# Conn_A.net
KiCad netlist of a schematic drawn in Altium Designer
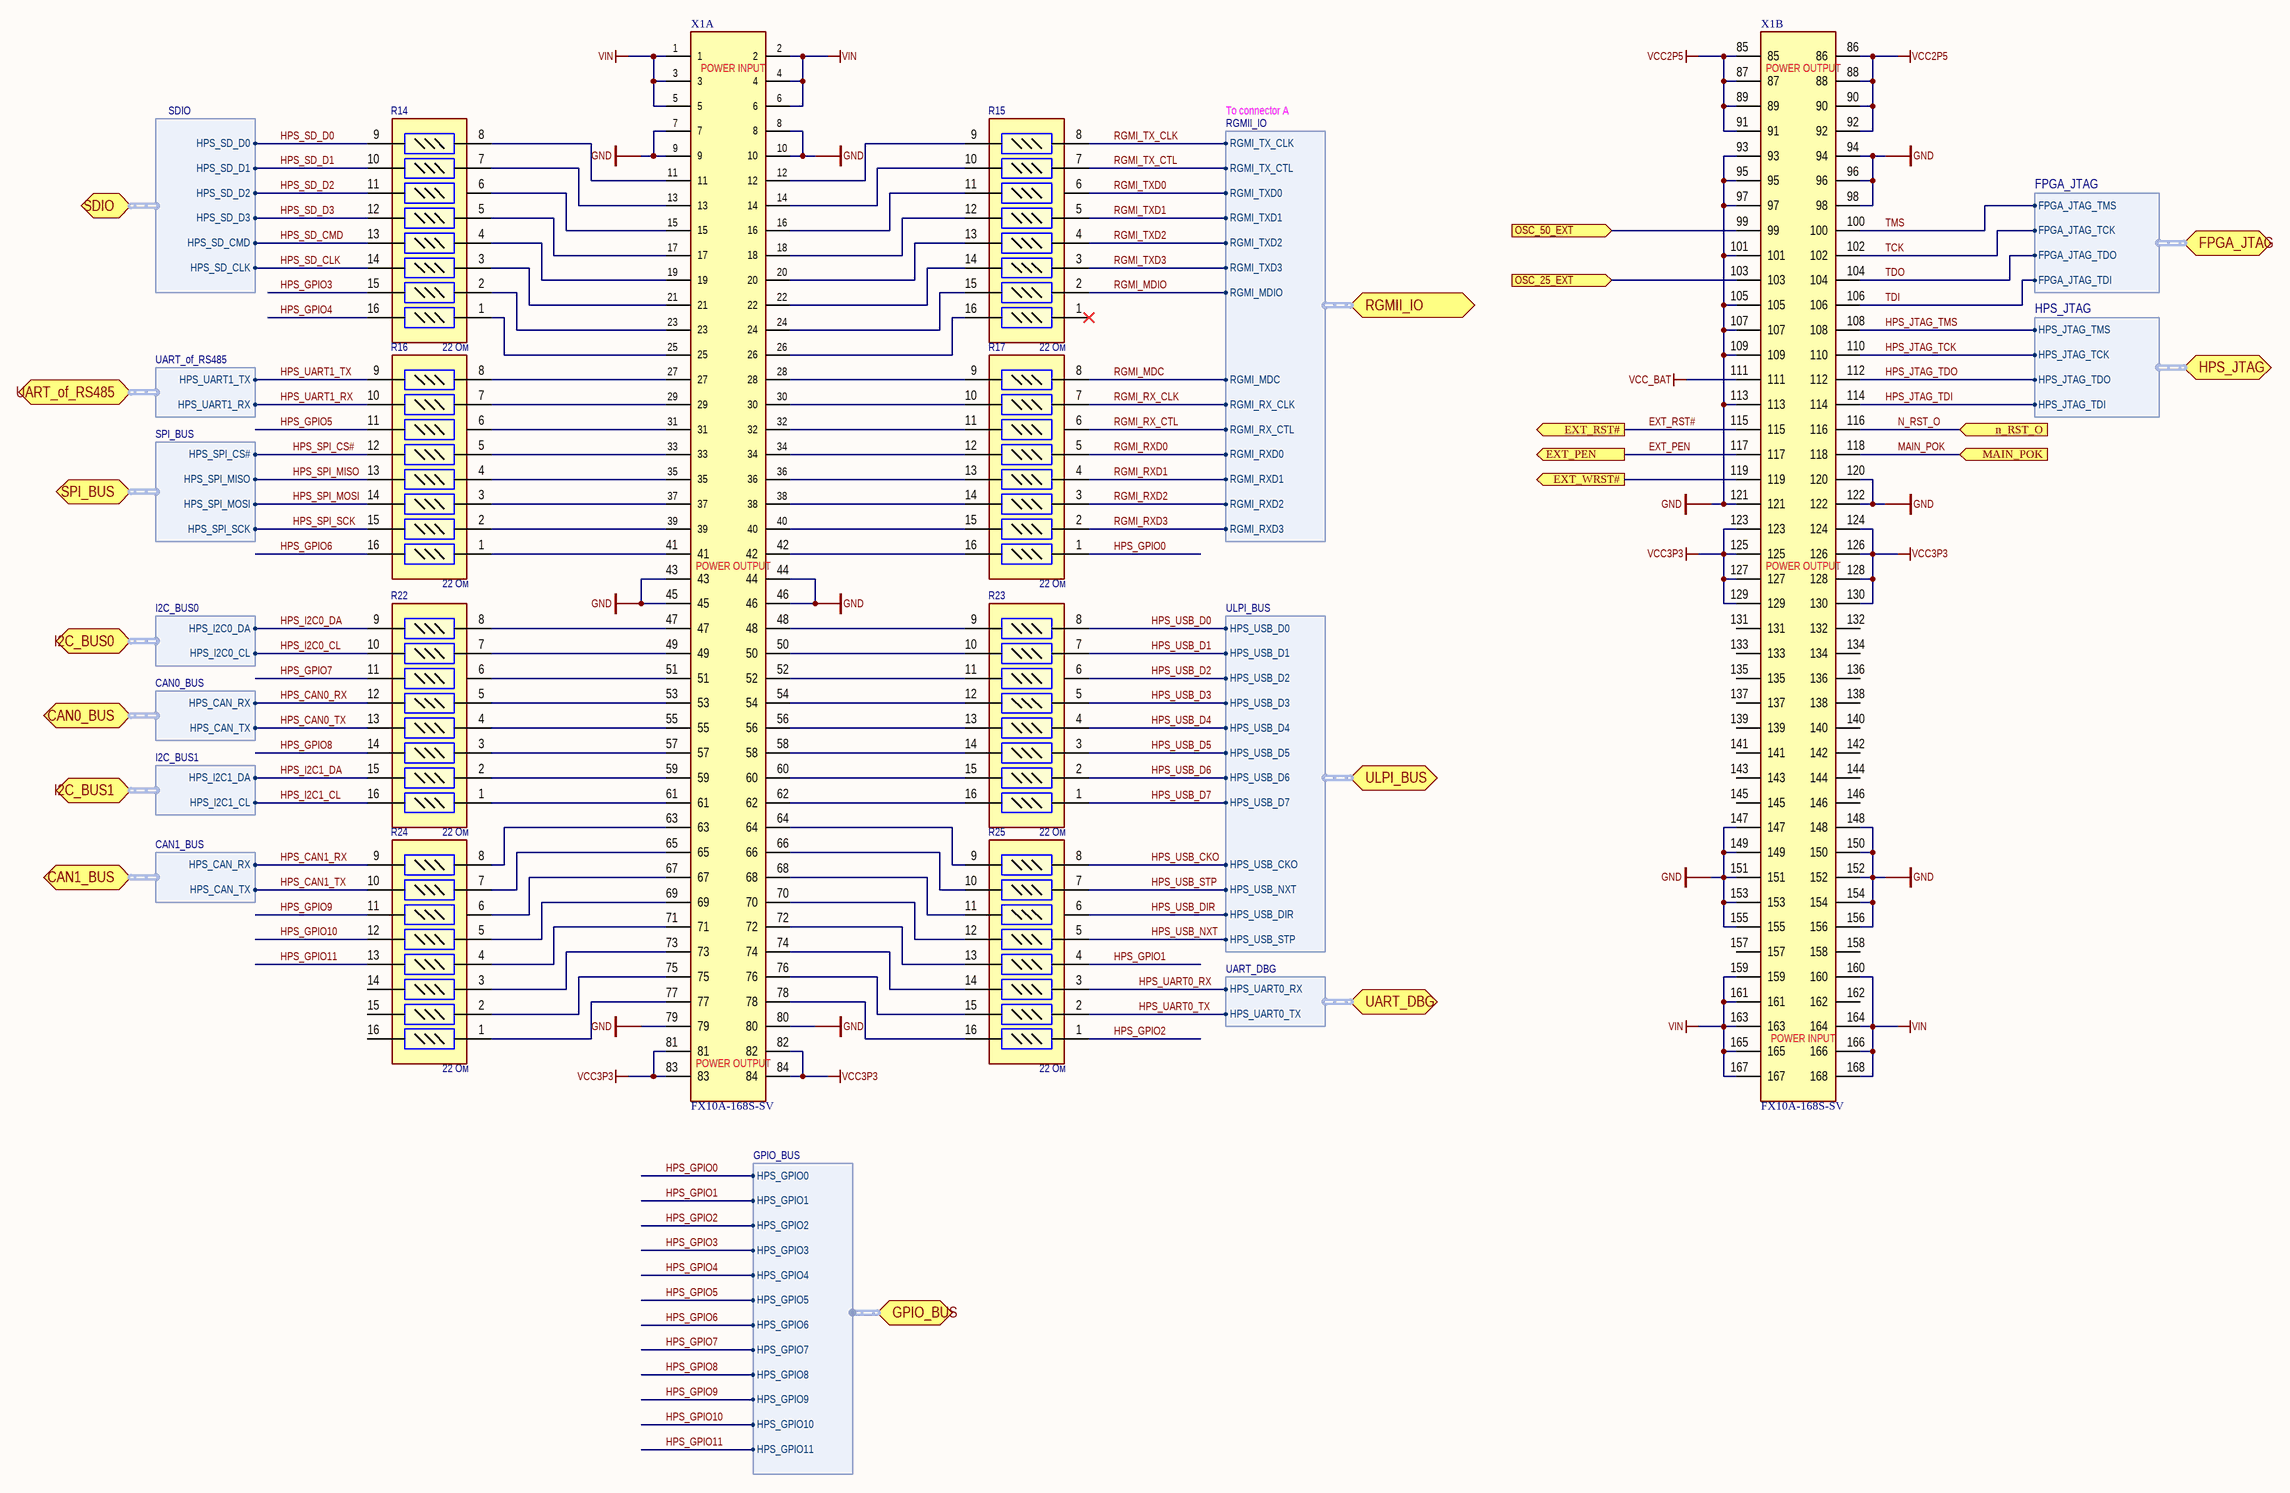
[diagram p0: Conn_A.SchDoc]

(export (version "E")
  (design (tool "Eeschema 10.0.6"))
  (components
    (comp (ref "R14")
      (value "22 Ом")
      (footprint "CAT16-J8")
      (description "Набор чип резисторов")
      (fields (field (name "Comment") "YC248-JR-07-22 Ом"))
      (libsource (lib "SD_IC") (part "YC248-JR-07-#"))
    )
    (comp (ref "R15")
      (value "22 Ом")
      (footprint "CAT16-J8")
      (description "Набор чип резисторов")
      (fields (field (name "Comment") "YC248-JR-07-22 Ом"))
      (libsource (lib "SD_IC") (part "YC248-JR-07-#"))
    )
    (comp (ref "R16")
      (value "22 Ом")
      (footprint "CAT16-J8")
      (description "Набор чип резисторов")
      (fields (field (name "Comment") "YC248-JR-07-22 Ом"))
      (libsource (lib "SD_IC") (part "YC248-JR-07-#"))
    )
    (comp (ref "R17")
      (value "22 Ом")
      (footprint "CAT16-J8")
      (description "Набор чип резисторов")
      (fields (field (name "Comment") "YC248-JR-07-22 Ом"))
      (libsource (lib "SD_IC") (part "YC248-JR-07-#"))
    )
    (comp (ref "R22")
      (value "22 Ом")
      (footprint "CAT16-J8")
      (description "Набор чип резисторов")
      (fields (field (name "Comment") "YC248-JR-07-22 Ом"))
      (libsource (lib "SD_IC") (part "YC248-JR-07-#"))
    )
    (comp (ref "R23")
      (value "22 Ом")
      (footprint "CAT16-J8")
      (description "Набор чип резисторов")
      (fields (field (name "Comment") "YC248-JR-07-22 Ом"))
      (libsource (lib "SD_IC") (part "YC248-JR-07-#"))
    )
    (comp (ref "R24")
      (value "22 Ом")
      (footprint "CAT16-J8")
      (description "Набор чип резисторов")
      (fields (field (name "Comment") "YC248-JR-07-22 Ом"))
      (libsource (lib "SD_IC") (part "YC248-JR-07-#"))
    )
    (comp (ref "R25")
      (value "22 Ом")
      (footprint "CAT16-J8")
      (description "Набор чип резисторов")
      (fields (field (name "Comment") "YC248-JR-07-22 Ом"))
      (libsource (lib "SD_IC") (part "YC248-JR-07-#"))
    )
    (comp (ref "X1")
      (value "FX10A-168S-SV")
      (footprint "FX10A-168S-SV")
      (libsource (lib "SD_IC") (part "FX10A-168S-SV"))
    )
  )
  (nets
    (net (code "14") (name "/EXT_PEN") (class "Default")
      (node (ref "X1") (pin "117") (pinfunction "117_117") (pintype "passive"))
    )
    (net (code "15") (name "/EXT_RST#") (class "Default")
      (node (ref "X1") (pin "115") (pinfunction "115_115") (pintype "passive"))
    )
    (net (code "16") (name "/EXT_WRST#") (class "Default")
      (node (ref "X1") (pin "119") (pinfunction "119_119") (pintype "passive"))
    )
    (net (code "17") (name "/HPS_CAN0_RX") (class "Default")
      (node (ref "R22") (pin "12") (pintype "passive"))
    )
    (net (code "18") (name "/HPS_CAN0_TX") (class "Default")
      (node (ref "R22") (pin "13") (pintype "passive"))
    )
    (net (code "19") (name "/HPS_CAN1_RX") (class "Default") (node (ref "R24") (pin "9") (pintype "passive")))
    (net (code "20") (name "/HPS_CAN1_TX") (class "Default")
      (node (ref "R24") (pin "10") (pintype "passive"))
    )
    (net (code "21") (name "/HPS_GPIO0") (class "Default") (node (ref "R17") (pin "1") (pintype "passive")))
    (net (code "22") (name "/HPS_GPIO1") (class "Default") (node (ref "R25") (pin "4") (pintype "passive")))
    (net (code "23") (name "/HPS_GPIO2") (class "Default") (node (ref "R25") (pin "1") (pintype "passive")))
    (net (code "24") (name "/HPS_GPIO3") (class "Default") (node (ref "R14") (pin "15") (pintype "passive")))
    (net (code "25") (name "/HPS_GPIO4") (class "Default") (node (ref "R14") (pin "16") (pintype "passive")))
    (net (code "26") (name "/HPS_GPIO5") (class "Default") (node (ref "R16") (pin "11") (pintype "passive")))
    (net (code "27") (name "/HPS_GPIO6") (class "Default") (node (ref "R16") (pin "16") (pintype "passive")))
    (net (code "28") (name "/HPS_GPIO7") (class "Default") (node (ref "R22") (pin "11") (pintype "passive")))
    (net (code "29") (name "/HPS_GPIO8") (class "Default") (node (ref "R22") (pin "14") (pintype "passive")))
    (net (code "30") (name "/HPS_GPIO9") (class "Default") (node (ref "R24") (pin "11") (pintype "passive")))
    (net (code "31") (name "/HPS_GPIO10") (class "Default") (node (ref "R24") (pin "12") (pintype "passive")))
    (net (code "32") (name "/HPS_GPIO11") (class "Default") (node (ref "R24") (pin "13") (pintype "passive")))
    (net (code "33") (name "/HPS_I2C0_CL") (class "Default")
      (node (ref "R22") (pin "10") (pintype "passive"))
    )
    (net (code "34") (name "/HPS_I2C0_DA") (class "Default") (node (ref "R22") (pin "9") (pintype "passive")))
    (net (code "35") (name "/HPS_I2C1_CL") (class "Default")
      (node (ref "R22") (pin "16") (pintype "passive"))
    )
    (net (code "36") (name "/HPS_I2C1_DA") (class "Default")
      (node (ref "R22") (pin "15") (pintype "passive"))
    )
    (net (code "37") (name "/HPS_JTAG_TCK") (class "Default")
      (node (ref "X1") (pin "110") (pinfunction "110_110") (pintype "passive"))
    )
    (net (code "38") (name "/HPS_JTAG_TDI") (class "Default")
      (node (ref "X1") (pin "114") (pinfunction "114_114") (pintype "passive"))
    )
    (net (code "39") (name "/HPS_JTAG_TDO") (class "Default")
      (node (ref "X1") (pin "112") (pinfunction "112_112") (pintype "passive"))
    )
    (net (code "40") (name "/HPS_JTAG_TMS") (class "Default")
      (node (ref "X1") (pin "108") (pinfunction "108_108") (pintype "passive"))
    )
    (net (code "41") (name "/HPS_SD_CLK") (class "Default") (node (ref "R14") (pin "14") (pintype "passive")))
    (net (code "42") (name "/HPS_SD_CMD") (class "Default") (node (ref "R14") (pin "13") (pintype "passive")))
    (net (code "43") (name "/HPS_SD_D0") (class "Default") (node (ref "R14") (pin "9") (pintype "passive")))
    (net (code "44") (name "/HPS_SD_D1") (class "Default") (node (ref "R14") (pin "10") (pintype "passive")))
    (net (code "45") (name "/HPS_SD_D2") (class "Default") (node (ref "R14") (pin "11") (pintype "passive")))
    (net (code "46") (name "/HPS_SD_D3") (class "Default") (node (ref "R14") (pin "12") (pintype "passive")))
    (net (code "47") (name "/HPS_SPI_CS#") (class "Default")
      (node (ref "R16") (pin "12") (pintype "passive"))
    )
    (net (code "48") (name "/HPS_SPI_MISO") (class "Default")
      (node (ref "R16") (pin "13") (pintype "passive"))
    )
    (net (code "49") (name "/HPS_SPI_MOSI") (class "Default")
      (node (ref "R16") (pin "14") (pintype "passive"))
    )
    (net (code "50") (name "/HPS_SPI_SCK") (class "Default")
      (node (ref "R16") (pin "15") (pintype "passive"))
    )
    (net (code "51") (name "/HPS_UART0_RX") (class "Default")
      (node (ref "R25") (pin "3") (pintype "passive"))
    )
    (net (code "52") (name "/HPS_UART0_TX") (class "Default")
      (node (ref "R25") (pin "2") (pintype "passive"))
    )
    (net (code "53") (name "/HPS_UART1_RX") (class "Default")
      (node (ref "R16") (pin "10") (pintype "passive"))
    )
    (net (code "54") (name "/HPS_UART1_TX") (class "Default")
      (node (ref "R16") (pin "9") (pintype "passive"))
    )
    (net (code "55") (name "/HPS_USB_CKO") (class "Default") (node (ref "R25") (pin "8") (pintype "passive")))
    (net (code "56") (name "/HPS_USB_D0") (class "Default") (node (ref "R23") (pin "8") (pintype "passive")))
    (net (code "57") (name "/HPS_USB_D1") (class "Default") (node (ref "R23") (pin "7") (pintype "passive")))
    (net (code "58") (name "/HPS_USB_D2") (class "Default") (node (ref "R23") (pin "6") (pintype "passive")))
    (net (code "59") (name "/HPS_USB_D3") (class "Default") (node (ref "R23") (pin "5") (pintype "passive")))
    (net (code "60") (name "/HPS_USB_D4") (class "Default") (node (ref "R23") (pin "4") (pintype "passive")))
    (net (code "61") (name "/HPS_USB_D5") (class "Default") (node (ref "R23") (pin "3") (pintype "passive")))
    (net (code "62") (name "/HPS_USB_D6") (class "Default") (node (ref "R23") (pin "2") (pintype "passive")))
    (net (code "63") (name "/HPS_USB_D7") (class "Default") (node (ref "R23") (pin "1") (pintype "passive")))
    (net (code "64") (name "/HPS_USB_DIR") (class "Default") (node (ref "R25") (pin "6") (pintype "passive")))
    (net (code "65") (name "/HPS_USB_NXT") (class "Default") (node (ref "R25") (pin "5") (pintype "passive")))
    (net (code "66") (name "/HPS_USB_STP") (class "Default") (node (ref "R25") (pin "7") (pintype "passive")))
    (net (code "67") (name "/MAIN_POK") (class "Default")
      (node (ref "X1") (pin "118") (pinfunction "118_118") (pintype "passive"))
    )
    (net (code "68") (name "/N_RST_O") (class "Default")
      (node (ref "X1") (pin "116") (pinfunction "116_116") (pintype "passive"))
    )
    (net (code "69") (name "/OSC_25_EXT") (class "Default")
      (node (ref "X1") (pin "103") (pinfunction "103_103") (pintype "passive"))
    )
    (net (code "70") (name "/OSC_50_EXT") (class "Default")
      (node (ref "X1") (pin "99") (pinfunction "99_99") (pintype "passive"))
    )
    (net (code "71") (name "/RGMI_MDC") (class "Default") (node (ref "R17") (pin "8") (pintype "passive")))
    (net (code "72") (name "/RGMI_MDIO") (class "Default") (node (ref "R15") (pin "2") (pintype "passive")))
    (net (code "73") (name "/RGMI_RXD0") (class "Default") (node (ref "R17") (pin "5") (pintype "passive")))
    (net (code "74") (name "/RGMI_RXD1") (class "Default") (node (ref "R17") (pin "4") (pintype "passive")))
    (net (code "75") (name "/RGMI_RXD2") (class "Default") (node (ref "R17") (pin "3") (pintype "passive")))
    (net (code "76") (name "/RGMI_RXD3") (class "Default") (node (ref "R17") (pin "2") (pintype "passive")))
    (net (code "77") (name "/RGMI_RX_CLK") (class "Default") (node (ref "R17") (pin "7") (pintype "passive")))
    (net (code "78") (name "/RGMI_RX_CTL") (class "Default") (node (ref "R17") (pin "6") (pintype "passive")))
    (net (code "79") (name "/RGMI_TXD0") (class "Default") (node (ref "R15") (pin "6") (pintype "passive")))
    (net (code "80") (name "/RGMI_TXD1") (class "Default") (node (ref "R15") (pin "5") (pintype "passive")))
    (net (code "81") (name "/RGMI_TXD2") (class "Default") (node (ref "R15") (pin "4") (pintype "passive")))
    (net (code "82") (name "/RGMI_TXD3") (class "Default") (node (ref "R15") (pin "3") (pintype "passive")))
    (net (code "83") (name "/RGMI_TX_CLK") (class "Default") (node (ref "R15") (pin "8") (pintype "passive")))
    (net (code "84") (name "/RGMI_TX_CTL") (class "Default") (node (ref "R15") (pin "7") (pintype "passive")))
    (net (code "85") (name "/TCK") (class "Default")
      (node (ref "X1") (pin "102") (pinfunction "102_102") (pintype "passive"))
    )
    (net (code "86") (name "/TDI") (class "Default")
      (node (ref "X1") (pin "106") (pinfunction "106_106") (pintype "passive"))
    )
    (net (code "87") (name "/TDO") (class "Default")
      (node (ref "X1") (pin "104") (pinfunction "104_104") (pintype "passive"))
    )
    (net (code "88") (name "/TMS") (class "Default")
      (node (ref "X1") (pin "100") (pinfunction "100_100") (pintype "passive"))
    )
    (net (code "102") (name "GND") (class "Default")
      (node (ref "X1") (pin "10") (pinfunction "10_10") (pintype "passive"))
      (node (ref "X1") (pin "101") (pinfunction "101_101") (pintype "passive"))
      (node (ref "X1") (pin "105") (pinfunction "105_105") (pintype "passive"))
      (node (ref "X1") (pin "107") (pinfunction "107_107") (pintype "passive"))
      (node (ref "X1") (pin "109") (pinfunction "109_109") (pintype "passive"))
      (node (ref "X1") (pin "113") (pinfunction "113_113") (pintype "passive"))
      (node (ref "X1") (pin "120") (pinfunction "120_120") (pintype "passive"))
      (node (ref "X1") (pin "121") (pinfunction "121_121") (pintype "passive"))
      (node (ref "X1") (pin "122") (pinfunction "122_122") (pintype "passive"))
      (node (ref "X1") (pin "147") (pinfunction "147_147") (pintype "passive"))
      (node (ref "X1") (pin "148") (pinfunction "148_148") (pintype "passive"))
      (node (ref "X1") (pin "149") (pinfunction "149_149") (pintype "passive"))
      (node (ref "X1") (pin "150") (pinfunction "150_150") (pintype "passive"))
      (node (ref "X1") (pin "151") (pinfunction "151_151") (pintype "passive"))
      (node (ref "X1") (pin "152") (pinfunction "152_152") (pintype "passive"))
      (node (ref "X1") (pin "153") (pinfunction "153_153") (pintype "passive"))
      (node (ref "X1") (pin "154") (pinfunction "154_154") (pintype "passive"))
      (node (ref "X1") (pin "155") (pinfunction "155_155") (pintype "passive"))
      (node (ref "X1") (pin "156") (pinfunction "156_156") (pintype "passive"))
      (node (ref "X1") (pin "43") (pinfunction "43_43") (pintype "passive"))
      (node (ref "X1") (pin "44") (pinfunction "44_44") (pintype "passive"))
      (node (ref "X1") (pin "45") (pinfunction "45_45") (pintype "passive"))
      (node (ref "X1") (pin "46") (pinfunction "46_46") (pintype "passive"))
      (node (ref "X1") (pin "7") (pinfunction "7_7") (pintype "passive"))
      (node (ref "X1") (pin "79") (pinfunction "79_79") (pintype "passive"))
      (node (ref "X1") (pin "8") (pinfunction "8_8") (pintype "passive"))
      (node (ref "X1") (pin "80") (pinfunction "80_80") (pintype "passive"))
      (node (ref "X1") (pin "9") (pinfunction "9_9") (pintype "passive"))
      (node (ref "X1") (pin "93") (pinfunction "93_93") (pintype "passive"))
      (node (ref "X1") (pin "94") (pinfunction "94_94") (pintype "passive"))
      (node (ref "X1") (pin "95") (pinfunction "95_95") (pintype "passive"))
      (node (ref "X1") (pin "96") (pinfunction "96_96") (pintype "passive"))
      (node (ref "X1") (pin "97") (pinfunction "97_97") (pintype "passive"))
      (node (ref "X1") (pin "98") (pinfunction "98_98") (pintype "passive"))
    )
    (net (code "103") (name "Net-(R14-Pad1)") (class "Default")
      (node (ref "R14") (pin "1") (pintype "passive"))
      (node (ref "X1") (pin "25") (pinfunction "25_25") (pintype "passive"))
    )
    (net (code "104") (name "Net-(R14-Pad2)") (class "Default")
      (node (ref "R14") (pin "2") (pintype "passive"))
      (node (ref "X1") (pin "23") (pinfunction "23_23") (pintype "passive"))
    )
    (net (code "105") (name "Net-(R14-Pad3)") (class "Default")
      (node (ref "R14") (pin "3") (pintype "passive"))
      (node (ref "X1") (pin "21") (pinfunction "21_21") (pintype "passive"))
    )
    (net (code "106") (name "Net-(R14-Pad4)") (class "Default")
      (node (ref "R14") (pin "4") (pintype "passive"))
      (node (ref "X1") (pin "19") (pinfunction "19_19") (pintype "passive"))
    )
    (net (code "107") (name "Net-(R14-Pad5)") (class "Default")
      (node (ref "R14") (pin "5") (pintype "passive"))
      (node (ref "X1") (pin "17") (pinfunction "17_17") (pintype "passive"))
    )
    (net (code "108") (name "Net-(R14-Pad6)") (class "Default")
      (node (ref "R14") (pin "6") (pintype "passive"))
      (node (ref "X1") (pin "15") (pinfunction "15_15") (pintype "passive"))
    )
    (net (code "109") (name "Net-(R14-Pad7)") (class "Default")
      (node (ref "R14") (pin "7") (pintype "passive"))
      (node (ref "X1") (pin "13") (pinfunction "13_13") (pintype "passive"))
    )
    (net (code "110") (name "Net-(R14-Pad8)") (class "Default")
      (node (ref "R14") (pin "8") (pintype "passive"))
      (node (ref "X1") (pin "11") (pinfunction "11_11") (pintype "passive"))
    )
    (net (code "111") (name "Net-(R15-Pad9)") (class "Default")
      (node (ref "R15") (pin "9") (pintype "passive"))
      (node (ref "X1") (pin "12") (pinfunction "12_12") (pintype "passive"))
    )
    (net (code "112") (name "Net-(R15-Pad10)") (class "Default")
      (node (ref "R15") (pin "10") (pintype "passive"))
      (node (ref "X1") (pin "14") (pinfunction "14_14") (pintype "passive"))
    )
    (net (code "113") (name "Net-(R15-Pad11)") (class "Default")
      (node (ref "R15") (pin "11") (pintype "passive"))
      (node (ref "X1") (pin "16") (pinfunction "16_16") (pintype "passive"))
    )
    (net (code "114") (name "Net-(R15-Pad12)") (class "Default")
      (node (ref "R15") (pin "12") (pintype "passive"))
      (node (ref "X1") (pin "18") (pinfunction "18_18") (pintype "passive"))
    )
    (net (code "115") (name "Net-(R15-Pad13)") (class "Default")
      (node (ref "R15") (pin "13") (pintype "passive"))
      (node (ref "X1") (pin "20") (pinfunction "20_20") (pintype "passive"))
    )
    (net (code "116") (name "Net-(R15-Pad14)") (class "Default")
      (node (ref "R15") (pin "14") (pintype "passive"))
      (node (ref "X1") (pin "22") (pinfunction "22_22") (pintype "passive"))
    )
    (net (code "117") (name "Net-(R15-Pad15)") (class "Default")
      (node (ref "R15") (pin "15") (pintype "passive"))
      (node (ref "X1") (pin "24") (pinfunction "24_24") (pintype "passive"))
    )
    (net (code "118") (name "Net-(R15-Pad16)") (class "Default")
      (node (ref "R15") (pin "16") (pintype "passive"))
      (node (ref "X1") (pin "26") (pinfunction "26_26") (pintype "passive"))
    )
    (net (code "119") (name "Net-(R16-Pad1)") (class "Default")
      (node (ref "R16") (pin "1") (pintype "passive"))
      (node (ref "X1") (pin "41") (pinfunction "41_41") (pintype "passive"))
    )
    (net (code "120") (name "Net-(R16-Pad2)") (class "Default")
      (node (ref "R16") (pin "2") (pintype "passive"))
      (node (ref "X1") (pin "39") (pinfunction "39_39") (pintype "passive"))
    )
    (net (code "121") (name "Net-(R16-Pad3)") (class "Default")
      (node (ref "R16") (pin "3") (pintype "passive"))
      (node (ref "X1") (pin "37") (pinfunction "37_37") (pintype "passive"))
    )
    (net (code "122") (name "Net-(R16-Pad4)") (class "Default")
      (node (ref "R16") (pin "4") (pintype "passive"))
      (node (ref "X1") (pin "35") (pinfunction "35_35") (pintype "passive"))
    )
    (net (code "123") (name "Net-(R16-Pad5)") (class "Default")
      (node (ref "R16") (pin "5") (pintype "passive"))
      (node (ref "X1") (pin "33") (pinfunction "33_33") (pintype "passive"))
    )
    (net (code "124") (name "Net-(R16-Pad6)") (class "Default")
      (node (ref "R16") (pin "6") (pintype "passive"))
      (node (ref "X1") (pin "31") (pinfunction "31_31") (pintype "passive"))
    )
    (net (code "125") (name "Net-(R16-Pad7)") (class "Default")
      (node (ref "R16") (pin "7") (pintype "passive"))
      (node (ref "X1") (pin "29") (pinfunction "29_29") (pintype "passive"))
    )
    (net (code "126") (name "Net-(R16-Pad8)") (class "Default")
      (node (ref "R16") (pin "8") (pintype "passive"))
      (node (ref "X1") (pin "27") (pinfunction "27_27") (pintype "passive"))
    )
    (net (code "127") (name "Net-(R17-Pad9)") (class "Default")
      (node (ref "R17") (pin "9") (pintype "passive"))
      (node (ref "X1") (pin "28") (pinfunction "28_28") (pintype "passive"))
    )
    (net (code "128") (name "Net-(R17-Pad10)") (class "Default")
      (node (ref "R17") (pin "10") (pintype "passive"))
      (node (ref "X1") (pin "30") (pinfunction "30_30") (pintype "passive"))
    )
    (net (code "129") (name "Net-(R17-Pad11)") (class "Default")
      (node (ref "R17") (pin "11") (pintype "passive"))
      (node (ref "X1") (pin "32") (pinfunction "32_32") (pintype "passive"))
    )
    (net (code "130") (name "Net-(R17-Pad12)") (class "Default")
      (node (ref "R17") (pin "12") (pintype "passive"))
      (node (ref "X1") (pin "34") (pinfunction "34_34") (pintype "passive"))
    )
    (net (code "131") (name "Net-(R17-Pad13)") (class "Default")
      (node (ref "R17") (pin "13") (pintype "passive"))
      (node (ref "X1") (pin "36") (pinfunction "36_36") (pintype "passive"))
    )
    (net (code "132") (name "Net-(R17-Pad14)") (class "Default")
      (node (ref "R17") (pin "14") (pintype "passive"))
      (node (ref "X1") (pin "38") (pinfunction "38_38") (pintype "passive"))
    )
    (net (code "133") (name "Net-(R17-Pad15)") (class "Default")
      (node (ref "R17") (pin "15") (pintype "passive"))
      (node (ref "X1") (pin "40") (pinfunction "40_40") (pintype "passive"))
    )
    (net (code "134") (name "Net-(R17-Pad16)") (class "Default")
      (node (ref "R17") (pin "16") (pintype "passive"))
      (node (ref "X1") (pin "42") (pinfunction "42_42") (pintype "passive"))
    )
    (net (code "135") (name "Net-(R22-Pad1)") (class "Default")
      (node (ref "R22") (pin "1") (pintype "passive"))
      (node (ref "X1") (pin "61") (pinfunction "61_61") (pintype "passive"))
    )
    (net (code "136") (name "Net-(R22-Pad2)") (class "Default")
      (node (ref "R22") (pin "2") (pintype "passive"))
      (node (ref "X1") (pin "59") (pinfunction "59_59") (pintype "passive"))
    )
    (net (code "137") (name "Net-(R22-Pad3)") (class "Default")
      (node (ref "R22") (pin "3") (pintype "passive"))
      (node (ref "X1") (pin "57") (pinfunction "57_57") (pintype "passive"))
    )
    (net (code "138") (name "Net-(R22-Pad4)") (class "Default")
      (node (ref "R22") (pin "4") (pintype "passive"))
      (node (ref "X1") (pin "55") (pinfunction "55_55") (pintype "passive"))
    )
    (net (code "139") (name "Net-(R22-Pad5)") (class "Default")
      (node (ref "R22") (pin "5") (pintype "passive"))
      (node (ref "X1") (pin "53") (pinfunction "53_53") (pintype "passive"))
    )
    (net (code "140") (name "Net-(R22-Pad6)") (class "Default")
      (node (ref "R22") (pin "6") (pintype "passive"))
      (node (ref "X1") (pin "51") (pinfunction "51_51") (pintype "passive"))
    )
    (net (code "141") (name "Net-(R22-Pad7)") (class "Default")
      (node (ref "R22") (pin "7") (pintype "passive"))
      (node (ref "X1") (pin "49") (pinfunction "49_49") (pintype "passive"))
    )
    (net (code "142") (name "Net-(R22-Pad8)") (class "Default")
      (node (ref "R22") (pin "8") (pintype "passive"))
      (node (ref "X1") (pin "47") (pinfunction "47_47") (pintype "passive"))
    )
    (net (code "143") (name "Net-(R23-Pad9)") (class "Default")
      (node (ref "R23") (pin "9") (pintype "passive"))
      (node (ref "X1") (pin "48") (pinfunction "48_48") (pintype "passive"))
    )
    (net (code "144") (name "Net-(R23-Pad10)") (class "Default")
      (node (ref "R23") (pin "10") (pintype "passive"))
      (node (ref "X1") (pin "50") (pinfunction "50_50") (pintype "passive"))
    )
    (net (code "145") (name "Net-(R23-Pad11)") (class "Default")
      (node (ref "R23") (pin "11") (pintype "passive"))
      (node (ref "X1") (pin "52") (pinfunction "52_52") (pintype "passive"))
    )
    (net (code "146") (name "Net-(R23-Pad12)") (class "Default")
      (node (ref "R23") (pin "12") (pintype "passive"))
      (node (ref "X1") (pin "54") (pinfunction "54_54") (pintype "passive"))
    )
    (net (code "147") (name "Net-(R23-Pad13)") (class "Default")
      (node (ref "R23") (pin "13") (pintype "passive"))
      (node (ref "X1") (pin "56") (pinfunction "56_56") (pintype "passive"))
    )
    (net (code "148") (name "Net-(R23-Pad14)") (class "Default")
      (node (ref "R23") (pin "14") (pintype "passive"))
      (node (ref "X1") (pin "58") (pinfunction "58_58") (pintype "passive"))
    )
    (net (code "149") (name "Net-(R23-Pad15)") (class "Default")
      (node (ref "R23") (pin "15") (pintype "passive"))
      (node (ref "X1") (pin "60") (pinfunction "60_60") (pintype "passive"))
    )
    (net (code "150") (name "Net-(R23-Pad16)") (class "Default")
      (node (ref "R23") (pin "16") (pintype "passive"))
      (node (ref "X1") (pin "62") (pinfunction "62_62") (pintype "passive"))
    )
    (net (code "151") (name "Net-(R24-Pad1)") (class "Default")
      (node (ref "R24") (pin "1") (pintype "passive"))
      (node (ref "X1") (pin "77") (pinfunction "77_77") (pintype "passive"))
    )
    (net (code "152") (name "Net-(R24-Pad2)") (class "Default")
      (node (ref "R24") (pin "2") (pintype "passive"))
      (node (ref "X1") (pin "75") (pinfunction "75_75") (pintype "passive"))
    )
    (net (code "153") (name "Net-(R24-Pad3)") (class "Default")
      (node (ref "R24") (pin "3") (pintype "passive"))
      (node (ref "X1") (pin "73") (pinfunction "73_73") (pintype "passive"))
    )
    (net (code "154") (name "Net-(R24-Pad4)") (class "Default")
      (node (ref "R24") (pin "4") (pintype "passive"))
      (node (ref "X1") (pin "71") (pinfunction "71_71") (pintype "passive"))
    )
    (net (code "155") (name "Net-(R24-Pad5)") (class "Default")
      (node (ref "R24") (pin "5") (pintype "passive"))
      (node (ref "X1") (pin "69") (pinfunction "69_69") (pintype "passive"))
    )
    (net (code "156") (name "Net-(R24-Pad6)") (class "Default")
      (node (ref "R24") (pin "6") (pintype "passive"))
      (node (ref "X1") (pin "67") (pinfunction "67_67") (pintype "passive"))
    )
    (net (code "157") (name "Net-(R24-Pad7)") (class "Default")
      (node (ref "R24") (pin "7") (pintype "passive"))
      (node (ref "X1") (pin "65") (pinfunction "65_65") (pintype "passive"))
    )
    (net (code "158") (name "Net-(R24-Pad8)") (class "Default")
      (node (ref "R24") (pin "8") (pintype "passive"))
      (node (ref "X1") (pin "63") (pinfunction "63_63") (pintype "passive"))
    )
    (net (code "159") (name "Net-(R25-Pad9)") (class "Default")
      (node (ref "R25") (pin "9") (pintype "passive"))
      (node (ref "X1") (pin "64") (pinfunction "64_64") (pintype "passive"))
    )
    (net (code "160") (name "Net-(R25-Pad10)") (class "Default")
      (node (ref "R25") (pin "10") (pintype "passive"))
      (node (ref "X1") (pin "66") (pinfunction "66_66") (pintype "passive"))
    )
    (net (code "161") (name "Net-(R25-Pad11)") (class "Default")
      (node (ref "R25") (pin "11") (pintype "passive"))
      (node (ref "X1") (pin "68") (pinfunction "68_68") (pintype "passive"))
    )
    (net (code "162") (name "Net-(R25-Pad12)") (class "Default")
      (node (ref "R25") (pin "12") (pintype "passive"))
      (node (ref "X1") (pin "70") (pinfunction "70_70") (pintype "passive"))
    )
    (net (code "163") (name "Net-(R25-Pad13)") (class "Default")
      (node (ref "R25") (pin "13") (pintype "passive"))
      (node (ref "X1") (pin "72") (pinfunction "72_72") (pintype "passive"))
    )
    (net (code "164") (name "Net-(R25-Pad14)") (class "Default")
      (node (ref "R25") (pin "14") (pintype "passive"))
      (node (ref "X1") (pin "74") (pinfunction "74_74") (pintype "passive"))
    )
    (net (code "165") (name "Net-(R25-Pad15)") (class "Default")
      (node (ref "R25") (pin "15") (pintype "passive"))
      (node (ref "X1") (pin "76") (pinfunction "76_76") (pintype "passive"))
    )
    (net (code "166") (name "Net-(R25-Pad16)") (class "Default")
      (node (ref "R25") (pin "16") (pintype "passive"))
      (node (ref "X1") (pin "78") (pinfunction "78_78") (pintype "passive"))
    )
    (net (code "167") (name "VCC2P5") (class "Default")
      (node (ref "X1") (pin "85") (pinfunction "85_85") (pintype "passive"))
      (node (ref "X1") (pin "86") (pinfunction "86_86") (pintype "passive"))
      (node (ref "X1") (pin "87") (pinfunction "87_87") (pintype "passive"))
      (node (ref "X1") (pin "88") (pinfunction "88_88") (pintype "passive"))
      (node (ref "X1") (pin "89") (pinfunction "89_89") (pintype "passive"))
      (node (ref "X1") (pin "90") (pinfunction "90_90") (pintype "passive"))
      (node (ref "X1") (pin "91") (pinfunction "91_91") (pintype "passive"))
      (node (ref "X1") (pin "92") (pinfunction "92_92") (pintype "passive"))
    )
    (net (code "168") (name "VCC3P3") (class "Default")
      (node (ref "X1") (pin "123") (pinfunction "123_123") (pintype "passive"))
      (node (ref "X1") (pin "124") (pinfunction "124_124") (pintype "passive"))
      (node (ref "X1") (pin "125") (pinfunction "125_125") (pintype "passive"))
      (node (ref "X1") (pin "126") (pinfunction "126_126") (pintype "passive"))
      (node (ref "X1") (pin "127") (pinfunction "127_127") (pintype "passive"))
      (node (ref "X1") (pin "128") (pinfunction "128_128") (pintype "passive"))
      (node (ref "X1") (pin "129") (pinfunction "129_129") (pintype "passive"))
      (node (ref "X1") (pin "130") (pinfunction "130_130") (pintype "passive"))
      (node (ref "X1") (pin "81") (pinfunction "81_81") (pintype "passive"))
      (node (ref "X1") (pin "82") (pinfunction "82_82") (pintype "passive"))
      (node (ref "X1") (pin "83") (pinfunction "83_83") (pintype "passive"))
      (node (ref "X1") (pin "84") (pinfunction "84_84") (pintype "passive"))
    )
    (net (code "169") (name "VCC_BAT") (class "Default")
      (node (ref "X1") (pin "111") (pinfunction "111_111") (pintype "passive"))
    )
    (net (code "170") (name "VIN") (class "Default")
      (node (ref "X1") (pin "1") (pinfunction "1_1") (pintype "passive"))
      (node (ref "X1") (pin "159") (pinfunction "159_159") (pintype "passive"))
      (node (ref "X1") (pin "160") (pinfunction "160_160") (pintype "passive"))
      (node (ref "X1") (pin "161") (pinfunction "161_161") (pintype "passive"))
      (node (ref "X1") (pin "163") (pinfunction "163_163") (pintype "passive"))
      (node (ref "X1") (pin "164") (pinfunction "164_164") (pintype "passive"))
      (node (ref "X1") (pin "165") (pinfunction "165_165") (pintype "passive"))
      (node (ref "X1") (pin "166") (pinfunction "166_166") (pintype "passive"))
      (node (ref "X1") (pin "167") (pinfunction "167_167") (pintype "passive"))
      (node (ref "X1") (pin "168") (pinfunction "168_168") (pintype "passive"))
      (node (ref "X1") (pin "2") (pinfunction "2_2") (pintype "passive"))
      (node (ref "X1") (pin "3") (pinfunction "3_3") (pintype "passive"))
      (node (ref "X1") (pin "4") (pinfunction "4_4") (pintype "passive"))
      (node (ref "X1") (pin "5") (pinfunction "5_5") (pintype "passive"))
      (node (ref "X1") (pin "6") (pinfunction "6_6") (pintype "passive"))
    )
    (net (code "171") (name "unconnected-(R15-Pad1)") (class "Default")
      (node (ref "R15") (pin "1") (pintype "passive+no_connect"))
    )
    (net (code "172") (name "unconnected-(R24-Pad14)") (class "Default")
      (node (ref "R24") (pin "14") (pintype "passive"))
    )
    (net (code "173") (name "unconnected-(R24-Pad15)") (class "Default")
      (node (ref "R24") (pin "15") (pintype "passive"))
    )
    (net (code "174") (name "unconnected-(R24-Pad16)") (class "Default")
      (node (ref "R24") (pin "16") (pintype "passive"))
    )
    (net (code "175") (name "unconnected-(X1-Pad131)") (class "Default")
      (node (ref "X1") (pin "131") (pinfunction "131_131") (pintype "passive"))
    )
    (net (code "176") (name "unconnected-(X1-Pad132)") (class "Default")
      (node (ref "X1") (pin "132") (pinfunction "132_132") (pintype "passive"))
    )
    (net (code "177") (name "unconnected-(X1-Pad133)") (class "Default")
      (node (ref "X1") (pin "133") (pinfunction "133_133") (pintype "passive"))
    )
    (net (code "178") (name "unconnected-(X1-Pad134)") (class "Default")
      (node (ref "X1") (pin "134") (pinfunction "134_134") (pintype "passive"))
    )
    (net (code "179") (name "unconnected-(X1-Pad135)") (class "Default")
      (node (ref "X1") (pin "135") (pinfunction "135_135") (pintype "passive"))
    )
    (net (code "180") (name "unconnected-(X1-Pad136)") (class "Default")
      (node (ref "X1") (pin "136") (pinfunction "136_136") (pintype "passive"))
    )
    (net (code "181") (name "unconnected-(X1-Pad137)") (class "Default")
      (node (ref "X1") (pin "137") (pinfunction "137_137") (pintype "passive"))
    )
    (net (code "182") (name "unconnected-(X1-Pad138)") (class "Default")
      (node (ref "X1") (pin "138") (pinfunction "138_138") (pintype "passive"))
    )
    (net (code "183") (name "unconnected-(X1-Pad139)") (class "Default")
      (node (ref "X1") (pin "139") (pinfunction "139_139") (pintype "passive"))
    )
    (net (code "184") (name "unconnected-(X1-Pad140)") (class "Default")
      (node (ref "X1") (pin "140") (pinfunction "140_140") (pintype "passive"))
    )
    (net (code "185") (name "unconnected-(X1-Pad141)") (class "Default")
      (node (ref "X1") (pin "141") (pinfunction "141_141") (pintype "passive"))
    )
    (net (code "186") (name "unconnected-(X1-Pad142)") (class "Default")
      (node (ref "X1") (pin "142") (pinfunction "142_142") (pintype "passive"))
    )
    (net (code "187") (name "unconnected-(X1-Pad143)") (class "Default")
      (node (ref "X1") (pin "143") (pinfunction "143_143") (pintype "passive"))
    )
    (net (code "188") (name "unconnected-(X1-Pad144)") (class "Default")
      (node (ref "X1") (pin "144") (pinfunction "144_144") (pintype "passive"))
    )
    (net (code "189") (name "unconnected-(X1-Pad145)") (class "Default")
      (node (ref "X1") (pin "145") (pinfunction "145_145") (pintype "passive"))
    )
    (net (code "190") (name "unconnected-(X1-Pad146)") (class "Default")
      (node (ref "X1") (pin "146") (pinfunction "146_146") (pintype "passive"))
    )
    (net (code "191") (name "unconnected-(X1-Pad157)") (class "Default")
      (node (ref "X1") (pin "157") (pinfunction "157_157") (pintype "passive"))
    )
    (net (code "192") (name "unconnected-(X1-Pad158)") (class "Default")
      (node (ref "X1") (pin "158") (pinfunction "158_158") (pintype "passive"))
    )
    (net (code "193") (name "unconnected-(X1-Pad162)") (class "Default")
      (node (ref "X1") (pin "162") (pinfunction "162_162") (pintype "passive"))
    )
  )
)
